# Sheet7.net
KiCad netlist of a schematic drawn in Altium Designer
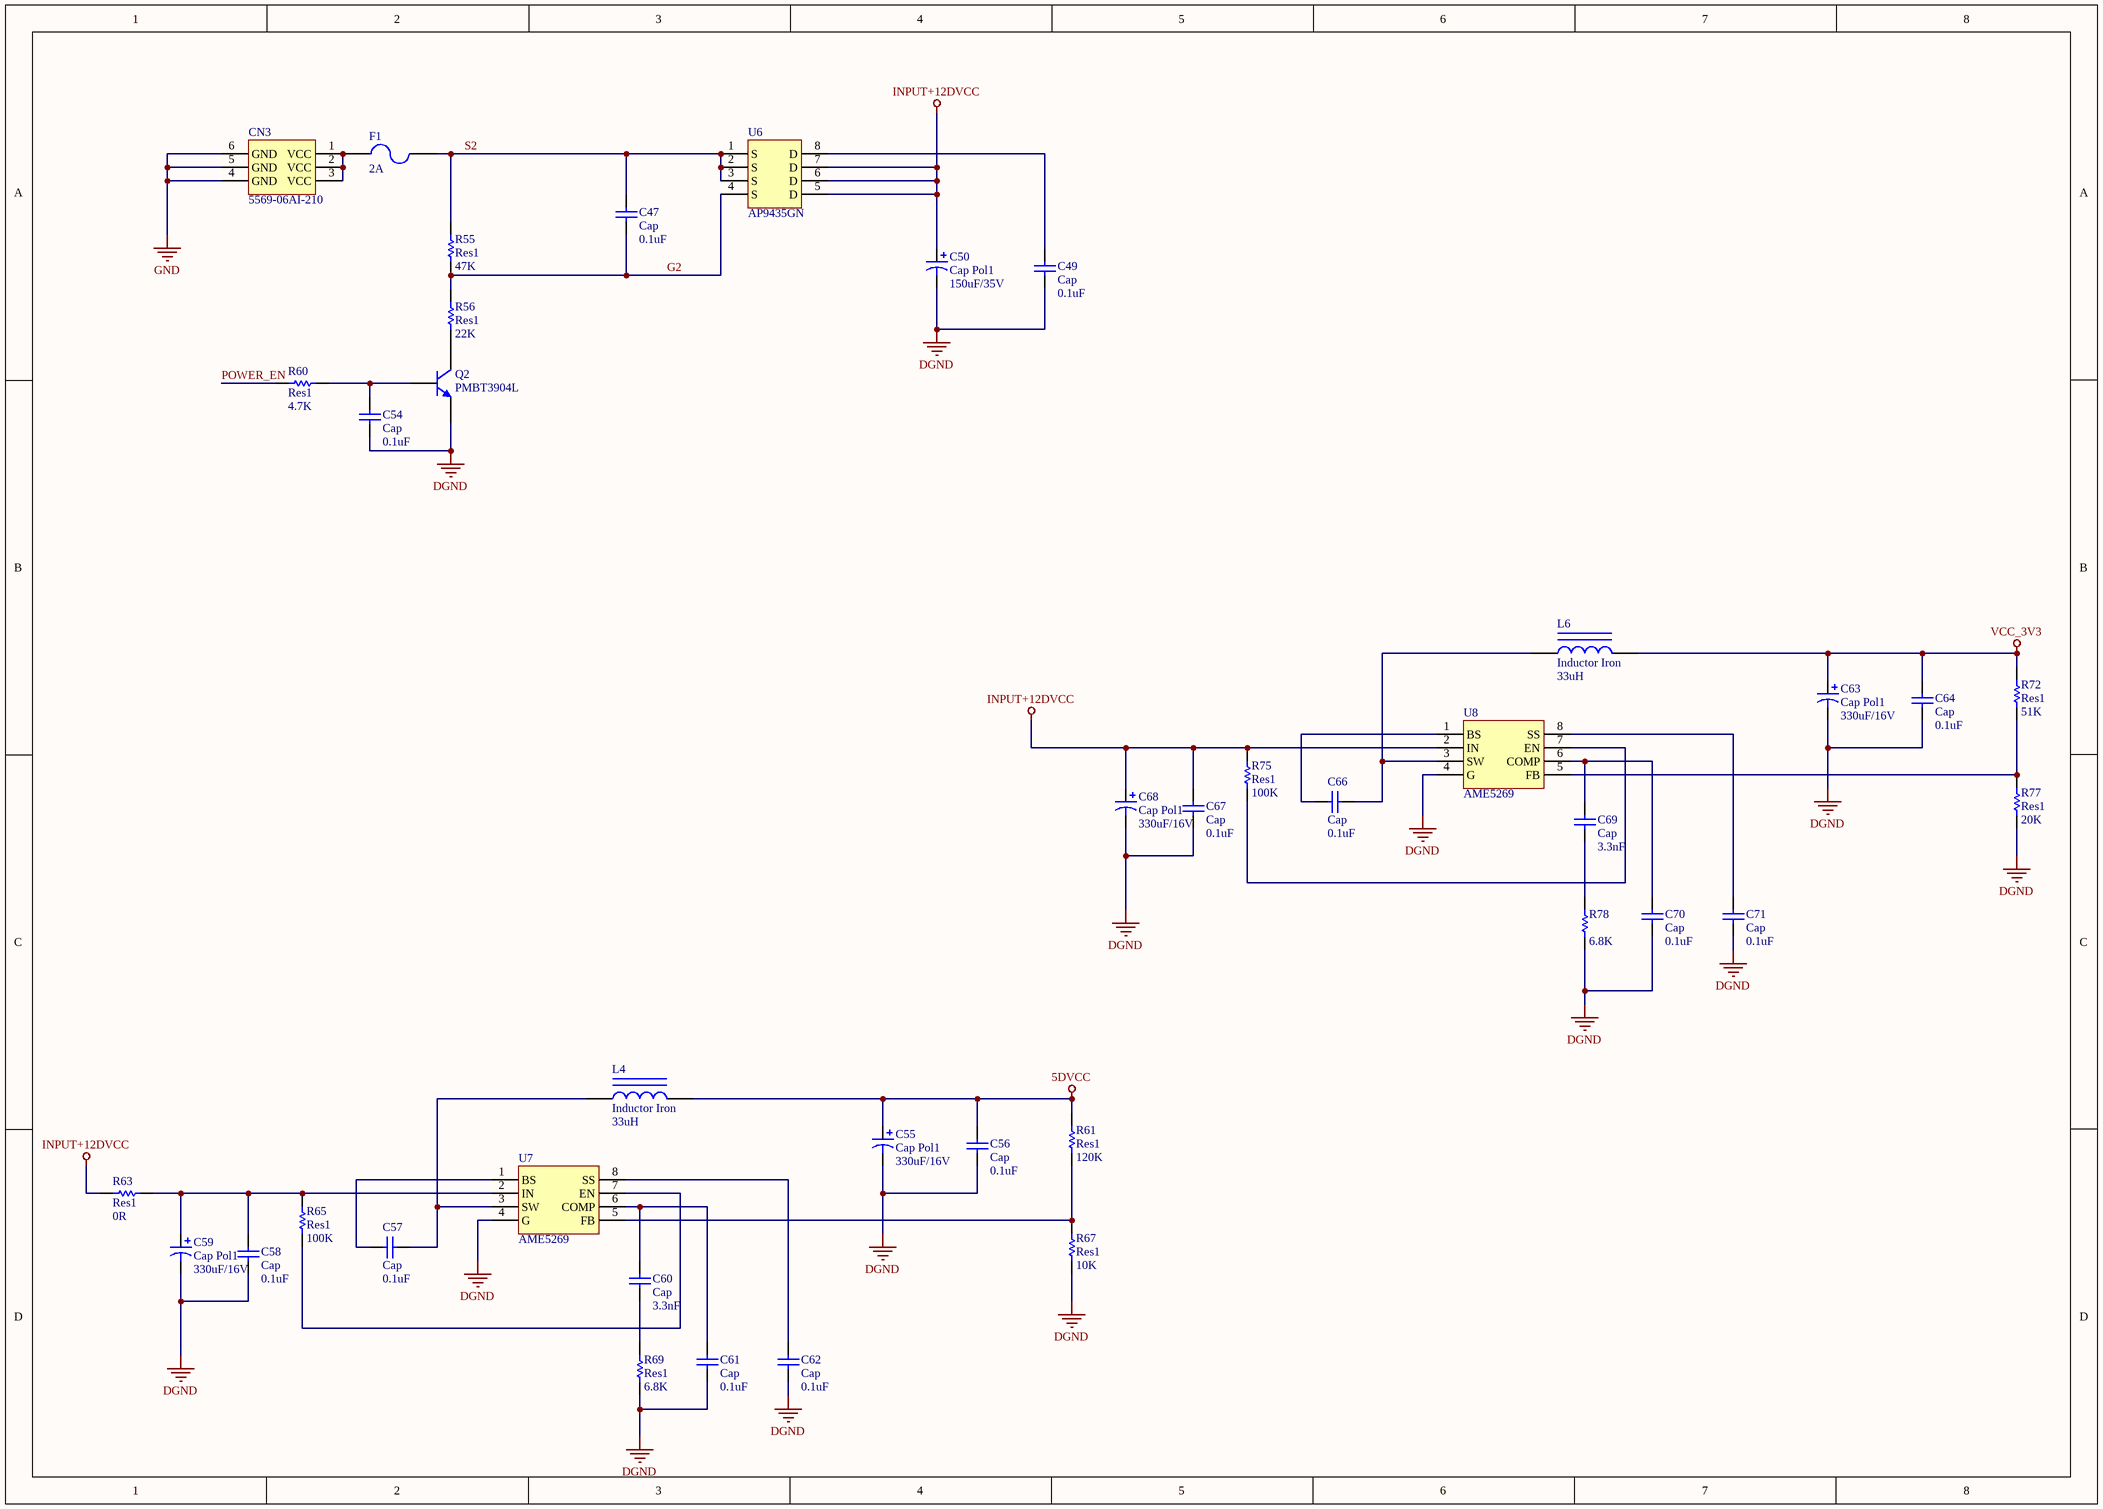
[diagram p0: Sheet7.SchDoc]

(export (version "E")
  (design (tool "Eeschema 10.0.6"))
  (components
    (comp (ref "C47")
      (value "Cap")
      (footprint "C-0402")
      (description "Capacitor")
      (fields (field (name "ALTIUM_VALUE") "0.1uF") (field (name "PUBLISHER") "Altium Limited"))
      (libsource (lib "Miscellaneous Devices") (part "Cap"))
    )
    (comp (ref "C49")
      (value "Cap")
      (footprint "C-0402")
      (description "Capacitor")
      (fields (field (name "ALTIUM_VALUE") "0.1uF") (field (name "PUBLISHER") "Altium Limited"))
      (libsource (lib "Miscellaneous Devices") (part "Cap"))
    )
    (comp (ref "C50")
      (value "Cap Pol1")
      (footprint "CE-D5.0")
      (description "Polarized Capacitor (Radial)")
      (fields (field (name "ALTIUM_VALUE") "150uF/35V") (field (name "PUBLISHER") "Altium Limited"))
      (libsource (lib "Miscellaneous Devices") (part "Cap Pol1"))
    )
    (comp (ref "C54")
      (value "Cap")
      (footprint "C-0402")
      (description "Capacitor")
      (fields (field (name "ALTIUM_VALUE") "0.1uF") (field (name "PUBLISHER") "Altium Limited"))
      (libsource (lib "Miscellaneous Devices") (part "Cap"))
    )
    (comp (ref "C55")
      (value "Cap Pol1")
      (footprint "C-0402")
      (description "Polarized Capacitor (Radial)")
      (fields (field (name "ALTIUM_VALUE") "330uF/16V") (field (name "PUBLISHER") "Altium Limited"))
      (libsource (lib "Miscellaneous Devices") (part "Cap Pol1"))
    )
    (comp (ref "C56")
      (value "Cap")
      (footprint "C-0402")
      (description "Capacitor")
      (fields (field (name "ALTIUM_VALUE") "0.1uF") (field (name "PUBLISHER") "Altium Limited"))
      (libsource (lib "Miscellaneous Devices") (part "Cap"))
    )
    (comp (ref "C57")
      (value "Cap")
      (footprint "C-0402")
      (description "Capacitor")
      (fields (field (name "ALTIUM_VALUE") "0.1uF") (field (name "PUBLISHER") "Altium Limited"))
      (libsource (lib "Miscellaneous Devices") (part "Cap"))
    )
    (comp (ref "C58")
      (value "Cap")
      (footprint "C-0402")
      (description "Capacitor")
      (fields (field (name "ALTIUM_VALUE") "0.1uF") (field (name "PUBLISHER") "Altium Limited"))
      (libsource (lib "Miscellaneous Devices") (part "Cap"))
    )
    (comp (ref "C59")
      (value "Cap Pol1")
      (footprint "CE-D3.6")
      (description "Polarized Capacitor (Radial)")
      (fields (field (name "ALTIUM_VALUE") "330uF/16V") (field (name "PUBLISHER") "Altium Limited"))
      (libsource (lib "Miscellaneous Devices") (part "Cap Pol1"))
    )
    (comp (ref "C60")
      (value "Cap")
      (footprint "C-0402")
      (description "Capacitor")
      (fields (field (name "ALTIUM_VALUE") "3.3nF") (field (name "PUBLISHER") "Altium Limited"))
      (libsource (lib "Miscellaneous Devices") (part "Cap"))
    )
    (comp (ref "C61")
      (value "Cap")
      (footprint "C-0402")
      (description "Capacitor")
      (fields (field (name "ALTIUM_VALUE") "0.1uF") (field (name "PUBLISHER") "Altium Limited"))
      (libsource (lib "Miscellaneous Devices") (part "Cap"))
    )
    (comp (ref "C62")
      (value "Cap")
      (footprint "C-0402")
      (description "Capacitor")
      (fields (field (name "ALTIUM_VALUE") "0.1uF") (field (name "PUBLISHER") "Altium Limited"))
      (libsource (lib "Miscellaneous Devices") (part "Cap"))
    )
    (comp (ref "C63")
      (value "Cap Pol1")
      (footprint "CE-D3.6")
      (description "Polarized Capacitor (Radial)")
      (fields (field (name "ALTIUM_VALUE") "330uF/16V") (field (name "PUBLISHER") "Altium Limited"))
      (libsource (lib "Miscellaneous Devices") (part "Cap Pol1"))
    )
    (comp (ref "C64")
      (value "Cap")
      (footprint "C-0402")
      (description "Capacitor")
      (fields (field (name "ALTIUM_VALUE") "0.1uF") (field (name "PUBLISHER") "Altium Limited"))
      (libsource (lib "Miscellaneous Devices") (part "Cap"))
    )
    (comp (ref "C66")
      (value "Cap")
      (footprint "C-0402")
      (description "Capacitor")
      (fields (field (name "ALTIUM_VALUE") "0.1uF") (field (name "PUBLISHER") "Altium Limited"))
      (libsource (lib "Miscellaneous Devices") (part "Cap"))
    )
    (comp (ref "C67")
      (value "Cap")
      (footprint "C-0402")
      (description "Capacitor")
      (fields (field (name "ALTIUM_VALUE") "0.1uF") (field (name "PUBLISHER") "Altium Limited"))
      (libsource (lib "Miscellaneous Devices") (part "Cap"))
    )
    (comp (ref "C68")
      (value "Cap Pol1")
      (footprint "CE-D3.6")
      (description "Polarized Capacitor (Radial)")
      (fields (field (name "ALTIUM_VALUE") "330uF/16V") (field (name "PUBLISHER") "Altium Limited"))
      (libsource (lib "Miscellaneous Devices") (part "Cap Pol1"))
    )
    (comp (ref "C69")
      (value "Cap")
      (footprint "C-0402")
      (description "Capacitor")
      (fields (field (name "ALTIUM_VALUE") "3.3nF") (field (name "PUBLISHER") "Altium Limited"))
      (libsource (lib "Miscellaneous Devices") (part "Cap"))
    )
    (comp (ref "C70")
      (value "Cap")
      (footprint "C-0402")
      (description "Capacitor")
      (fields (field (name "ALTIUM_VALUE") "0.1uF") (field (name "PUBLISHER") "Altium Limited"))
      (libsource (lib "Miscellaneous Devices") (part "Cap"))
    )
    (comp (ref "C71")
      (value "Cap")
      (footprint "C-0402")
      (description "Capacitor")
      (fields (field (name "ALTIUM_VALUE") "0.1uF") (field (name "PUBLISHER") "Altium Limited"))
      (libsource (lib "Miscellaneous Devices") (part "Cap"))
    )
    (comp (ref "CN3")
      (value "5569-06AI-210")
      (footprint "SOT23-6_L")
      (libsource (lib "Schlib1") (part "5569-06AI-210"))
    )
    (comp (ref "F1")
      (value "2A")
      (footprint "R-1206")
      (description "Fuse")
      (fields (field (name "PUBLISHER") "Altium Limited"))
      (libsource (lib "Miscellaneous Devices") (part "Fuse 2"))
    )
    (comp (ref "L4")
      (value "Inductor Iron")
      (footprint "INDC4532")
      (description "Magnetic-Core Inductor")
      (fields (field (name "ALTIUM_VALUE") "33uH") (field (name "PUBLISHER") "Altium Limited"))
      (libsource (lib "Miscellaneous Devices") (part "Inductor Iron"))
    )
    (comp (ref "L6")
      (value "Inductor Iron")
      (footprint "INDC4532")
      (description "Magnetic-Core Inductor")
      (fields (field (name "ALTIUM_VALUE") "33uH") (field (name "PUBLISHER") "Altium Limited"))
      (libsource (lib "Miscellaneous Devices") (part "Inductor Iron"))
    )
    (comp (ref "Q2")
      (value "PMBT3904L")
      (footprint "Q-SOT23")
      (description "NPN General Purpose Amplifier")
      (fields (field (name "PUBLISHER") "Altium Limited"))
      (libsource (lib "Miscellaneous Devices") (part "2N3904"))
    )
    (comp (ref "R55")
      (value "Res1")
      (footprint "R-0603")
      (description "Resistor")
      (fields (field (name "ALTIUM_VALUE") "47K") (field (name "PUBLISHER") "Altium Limited"))
      (libsource (lib "Miscellaneous Devices") (part "Res1"))
    )
    (comp (ref "R56")
      (value "Res1")
      (footprint "R-0603")
      (description "Resistor")
      (fields (field (name "ALTIUM_VALUE") "22K") (field (name "PUBLISHER") "Altium Limited"))
      (libsource (lib "Miscellaneous Devices") (part "Res1"))
    )
    (comp (ref "R60")
      (value "Res1")
      (footprint "R-0603")
      (description "Resistor")
      (fields (field (name "ALTIUM_VALUE") "4.7K") (field (name "PUBLISHER") "Altium Limited"))
      (libsource (lib "Miscellaneous Devices") (part "Res1"))
    )
    (comp (ref "R61")
      (value "Res1")
      (footprint "R-0603")
      (description "Resistor")
      (fields (field (name "ALTIUM_VALUE") "120K") (field (name "PUBLISHER") "Altium Limited"))
      (libsource (lib "Miscellaneous Devices") (part "Res1"))
    )
    (comp (ref "R63")
      (value "Res1")
      (footprint "R-0603")
      (description "Resistor")
      (fields (field (name "ALTIUM_VALUE") "0R") (field (name "PUBLISHER") "Altium Limited"))
      (libsource (lib "Miscellaneous Devices") (part "Res1"))
    )
    (comp (ref "R65")
      (value "Res1")
      (footprint "R-0603")
      (description "Resistor")
      (fields (field (name "ALTIUM_VALUE") "100K") (field (name "PUBLISHER") "Altium Limited"))
      (libsource (lib "Miscellaneous Devices") (part "Res1"))
    )
    (comp (ref "R67")
      (value "Res1")
      (footprint "R-0603")
      (description "Resistor")
      (fields (field (name "ALTIUM_VALUE") "10K") (field (name "PUBLISHER") "Altium Limited"))
      (libsource (lib "Miscellaneous Devices") (part "Res1"))
    )
    (comp (ref "R69")
      (value "Res1")
      (footprint "R-0603")
      (description "Resistor")
      (fields (field (name "ALTIUM_VALUE") "6.8K") (field (name "PUBLISHER") "Altium Limited"))
      (libsource (lib "Miscellaneous Devices") (part "Res1"))
    )
    (comp (ref "R72")
      (value "Res1")
      (footprint "R-0603")
      (description "Resistor")
      (fields (field (name "ALTIUM_VALUE") "51K") (field (name "PUBLISHER") "Altium Limited"))
      (libsource (lib "Miscellaneous Devices") (part "Res1"))
    )
    (comp (ref "R75")
      (value "Res1")
      (footprint "R-0603")
      (description "Resistor")
      (fields (field (name "ALTIUM_VALUE") "100K") (field (name "PUBLISHER") "Altium Limited"))
      (libsource (lib "Miscellaneous Devices") (part "Res1"))
    )
    (comp (ref "R77")
      (value "Res1")
      (footprint "R-0603")
      (description "Resistor")
      (fields (field (name "ALTIUM_VALUE") "20K") (field (name "PUBLISHER") "Altium Limited"))
      (libsource (lib "Miscellaneous Devices") (part "Res1"))
    )
    (comp (ref "R78")
      (value "6.8K")
      (footprint "R-0603")
      (description "Resistor")
      (fields (field (name "Comment") "Res1") (field (name "PUBLISHER") "Altium Limited"))
      (libsource (lib "Miscellaneous Devices") (part "Res1"))
    )
    (comp (ref "U6") (value "AP9435GN") (footprint "U-SOP/1.3") (libsource (lib "Schlib1") (part "AP9435GN")))
    (comp (ref "U7") (value "AME5269") (footprint "U-SOP/1.3") (libsource (lib "Schlib1") (part "AME5269")))
    (comp (ref "U8") (value "AME5269") (footprint "U-SOP/1.3") (libsource (lib "Schlib1") (part "AME5269")))
  )
  (nets
    (net (code "1") (name "/G2") (class "Default")
      (node (ref "C47") (pin "1") (pinfunction "1_1") (pintype "passive"))
      (node (ref "R55") (pin "1") (pinfunction "1_1") (pintype "passive"))
      (node (ref "R56") (pin "2") (pinfunction "2_2") (pintype "passive"))
      (node (ref "U6") (pin "4") (pinfunction "S_4") (pintype "passive"))
    )
    (net (code "2") (name "/POWER_EN") (class "Default")
      (node (ref "R60") (pin "2") (pinfunction "2_2") (pintype "passive"))
    )
    (net (code "3") (name "/S2") (class "Default")
      (node (ref "C47") (pin "2") (pinfunction "2_2") (pintype "passive"))
      (node (ref "F1") (pin "2") (pinfunction "2_2") (pintype "passive"))
      (node (ref "R55") (pin "2") (pinfunction "2_2") (pintype "passive"))
      (node (ref "U6") (pin "1") (pinfunction "S_1") (pintype "passive"))
      (node (ref "U6") (pin "2") (pinfunction "S_2") (pintype "passive"))
      (node (ref "U6") (pin "3") (pinfunction "S_3") (pintype "passive"))
    )
    (net (code "4") (name "5DVCC") (class "Default")
      (node (ref "C55") (pin "1") (pinfunction "1_1") (pintype "passive"))
      (node (ref "C56") (pin "1") (pinfunction "1_1") (pintype "passive"))
      (node (ref "L4") (pin "2") (pinfunction "2_2") (pintype "passive"))
      (node (ref "R61") (pin "1") (pinfunction "1_1") (pintype "passive"))
    )
    (net (code "5") (name "DGND") (class "Default")
      (node (ref "C49") (pin "1") (pinfunction "1_1") (pintype "passive"))
      (node (ref "C50") (pin "2") (pinfunction "2_2") (pintype "passive"))
      (node (ref "C54") (pin "1") (pinfunction "1_1") (pintype "passive"))
      (node (ref "C55") (pin "2") (pinfunction "2_2") (pintype "passive"))
      (node (ref "C56") (pin "2") (pinfunction "2_2") (pintype "passive"))
      (node (ref "C58") (pin "2") (pinfunction "2_2") (pintype "passive"))
      (node (ref "C59") (pin "2") (pinfunction "2_2") (pintype "passive"))
      (node (ref "C61") (pin "2") (pinfunction "2_2") (pintype "passive"))
      (node (ref "C62") (pin "2") (pinfunction "2_2") (pintype "passive"))
      (node (ref "C63") (pin "2") (pinfunction "2_2") (pintype "passive"))
      (node (ref "C64") (pin "2") (pinfunction "2_2") (pintype "passive"))
      (node (ref "C67") (pin "2") (pinfunction "2_2") (pintype "passive"))
      (node (ref "C68") (pin "2") (pinfunction "2_2") (pintype "passive"))
      (node (ref "C70") (pin "2") (pinfunction "2_2") (pintype "passive"))
      (node (ref "C71") (pin "2") (pinfunction "2_2") (pintype "passive"))
      (node (ref "Q2") (pin "1") (pinfunction "E_1") (pintype "passive"))
      (node (ref "R67") (pin "2") (pinfunction "2_2") (pintype "passive"))
      (node (ref "R69") (pin "2") (pinfunction "2_2") (pintype "passive"))
      (node (ref "R77") (pin "2") (pinfunction "2_2") (pintype "passive"))
      (node (ref "R78") (pin "2") (pinfunction "2_2") (pintype "passive"))
      (node (ref "U7") (pin "4") (pinfunction "G_4") (pintype "passive"))
      (node (ref "U8") (pin "4") (pinfunction "G_4") (pintype "passive"))
    )
    (net (code "6") (name "GND") (class "Default")
      (node (ref "CN3") (pin "4") (pinfunction "GND_4") (pintype "passive"))
      (node (ref "CN3") (pin "5") (pinfunction "GND_5") (pintype "passive"))
      (node (ref "CN3") (pin "6") (pinfunction "GND_6") (pintype "passive"))
    )
    (net (code "7") (name "INPUT+12DVCC") (class "Default")
      (node (ref "C50") (pin "1") (pinfunction "1_1") (pintype "passive"))
      (node (ref "C67") (pin "1") (pinfunction "1_1") (pintype "passive"))
      (node (ref "C68") (pin "1") (pinfunction "1_1") (pintype "passive"))
      (node (ref "R63") (pin "1") (pinfunction "1_1") (pintype "passive"))
      (node (ref "R75") (pin "1") (pinfunction "1_1") (pintype "passive"))
      (node (ref "U6") (pin "5") (pinfunction "D_5") (pintype "passive"))
      (node (ref "U6") (pin "6") (pinfunction "D_6") (pintype "passive"))
      (node (ref "U6") (pin "7") (pinfunction "D_7") (pintype "passive"))
      (node (ref "U8") (pin "2") (pinfunction "IN_2") (pintype "passive"))
    )
    (net (code "8") (name "Net-(C49-Pad2)") (class "Default")
      (node (ref "C49") (pin "2") (pinfunction "2_2") (pintype "passive"))
      (node (ref "U6") (pin "8") (pinfunction "D_8") (pintype "passive"))
    )
    (net (code "9") (name "Net-(C60-Pad2)") (class "Default")
      (node (ref "C60") (pin "2") (pinfunction "2_2") (pintype "passive"))
      (node (ref "R69") (pin "1") (pinfunction "1_1") (pintype "passive"))
    )
    (net (code "10") (name "Net-(C69-Pad2)") (class "Default")
      (node (ref "C69") (pin "2") (pinfunction "2_2") (pintype "passive"))
      (node (ref "R78") (pin "1") (pinfunction "1_1") (pintype "passive"))
    )
    (net (code "11") (name "Net-(CN3-VCC-Pad1)") (class "Default")
      (node (ref "CN3") (pin "1") (pinfunction "VCC_1") (pintype "passive"))
      (node (ref "CN3") (pin "2") (pinfunction "VCC_2") (pintype "passive"))
      (node (ref "CN3") (pin "3") (pinfunction "VCC_3") (pintype "passive"))
      (node (ref "F1") (pin "1") (pinfunction "1_1") (pintype "passive"))
    )
    (net (code "12") (name "Net-(Q2-B)") (class "Default")
      (node (ref "C54") (pin "2") (pinfunction "2_2") (pintype "passive"))
      (node (ref "Q2") (pin "2") (pinfunction "B_2") (pintype "passive"))
      (node (ref "R60") (pin "1") (pinfunction "1_1") (pintype "passive"))
    )
    (net (code "13") (name "Net-(Q2-C)") (class "Default")
      (node (ref "Q2") (pin "3") (pinfunction "C_3") (pintype "passive"))
      (node (ref "R56") (pin "1") (pinfunction "1_1") (pintype "passive"))
    )
    (net (code "14") (name "Net-(U7-BS)") (class "Default")
      (node (ref "C57") (pin "2") (pinfunction "2_2") (pintype "passive"))
      (node (ref "U7") (pin "1") (pinfunction "BS_1") (pintype "passive"))
    )
    (net (code "15") (name "Net-(U7-COMP)") (class "Default")
      (node (ref "C60") (pin "1") (pinfunction "1_1") (pintype "passive"))
      (node (ref "C61") (pin "1") (pinfunction "1_1") (pintype "passive"))
      (node (ref "U7") (pin "6") (pinfunction "COMP_6") (pintype "passive"))
    )
    (net (code "16") (name "Net-(U7-EN)") (class "Default")
      (node (ref "R65") (pin "2") (pinfunction "2_2") (pintype "passive"))
      (node (ref "U7") (pin "7") (pinfunction "EN_7") (pintype "passive"))
    )
    (net (code "17") (name "Net-(U7-FB)") (class "Default")
      (node (ref "R61") (pin "2") (pinfunction "2_2") (pintype "passive"))
      (node (ref "R67") (pin "1") (pinfunction "1_1") (pintype "passive"))
      (node (ref "U7") (pin "5") (pinfunction "FB_5") (pintype "passive"))
    )
    (net (code "18") (name "Net-(U7-IN)") (class "Default")
      (node (ref "C58") (pin "1") (pinfunction "1_1") (pintype "passive"))
      (node (ref "C59") (pin "1") (pinfunction "1_1") (pintype "passive"))
      (node (ref "R63") (pin "2") (pinfunction "2_2") (pintype "passive"))
      (node (ref "R65") (pin "1") (pinfunction "1_1") (pintype "passive"))
      (node (ref "U7") (pin "2") (pinfunction "IN_2") (pintype "passive"))
    )
    (net (code "19") (name "Net-(U7-SS)") (class "Default")
      (node (ref "C62") (pin "1") (pinfunction "1_1") (pintype "passive"))
      (node (ref "U7") (pin "8") (pinfunction "SS_8") (pintype "passive"))
    )
    (net (code "20") (name "Net-(U7-SW)") (class "Default")
      (node (ref "C57") (pin "1") (pinfunction "1_1") (pintype "passive"))
      (node (ref "L4") (pin "1") (pinfunction "1_1") (pintype "passive"))
      (node (ref "U7") (pin "3") (pinfunction "SW_3") (pintype "passive"))
    )
    (net (code "21") (name "Net-(U8-BS)") (class "Default")
      (node (ref "C66") (pin "2") (pinfunction "2_2") (pintype "passive"))
      (node (ref "U8") (pin "1") (pinfunction "BS_1") (pintype "passive"))
    )
    (net (code "22") (name "Net-(U8-COMP)") (class "Default")
      (node (ref "C69") (pin "1") (pinfunction "1_1") (pintype "passive"))
      (node (ref "C70") (pin "1") (pinfunction "1_1") (pintype "passive"))
      (node (ref "U8") (pin "6") (pinfunction "COMP_6") (pintype "passive"))
    )
    (net (code "23") (name "Net-(U8-EN)") (class "Default")
      (node (ref "R75") (pin "2") (pinfunction "2_2") (pintype "passive"))
      (node (ref "U8") (pin "7") (pinfunction "EN_7") (pintype "passive"))
    )
    (net (code "24") (name "Net-(U8-FB)") (class "Default")
      (node (ref "R72") (pin "2") (pinfunction "2_2") (pintype "passive"))
      (node (ref "R77") (pin "1") (pinfunction "1_1") (pintype "passive"))
      (node (ref "U8") (pin "5") (pinfunction "FB_5") (pintype "passive"))
    )
    (net (code "25") (name "Net-(U8-SS)") (class "Default")
      (node (ref "C71") (pin "1") (pinfunction "1_1") (pintype "passive"))
      (node (ref "U8") (pin "8") (pinfunction "SS_8") (pintype "passive"))
    )
    (net (code "26") (name "Net-(U8-SW)") (class "Default")
      (node (ref "C66") (pin "1") (pinfunction "1_1") (pintype "passive"))
      (node (ref "L6") (pin "1") (pinfunction "1_1") (pintype "passive"))
      (node (ref "U8") (pin "3") (pinfunction "SW_3") (pintype "passive"))
    )
    (net (code "27") (name "VCC_3V3") (class "Default")
      (node (ref "C63") (pin "1") (pinfunction "1_1") (pintype "passive"))
      (node (ref "C64") (pin "1") (pinfunction "1_1") (pintype "passive"))
      (node (ref "L6") (pin "2") (pinfunction "2_2") (pintype "passive"))
      (node (ref "R72") (pin "1") (pinfunction "1_1") (pintype "passive"))
    )
  )
)
